# rwr_schematic.net
KiCad netlist of a schematic drawn in EAGLE
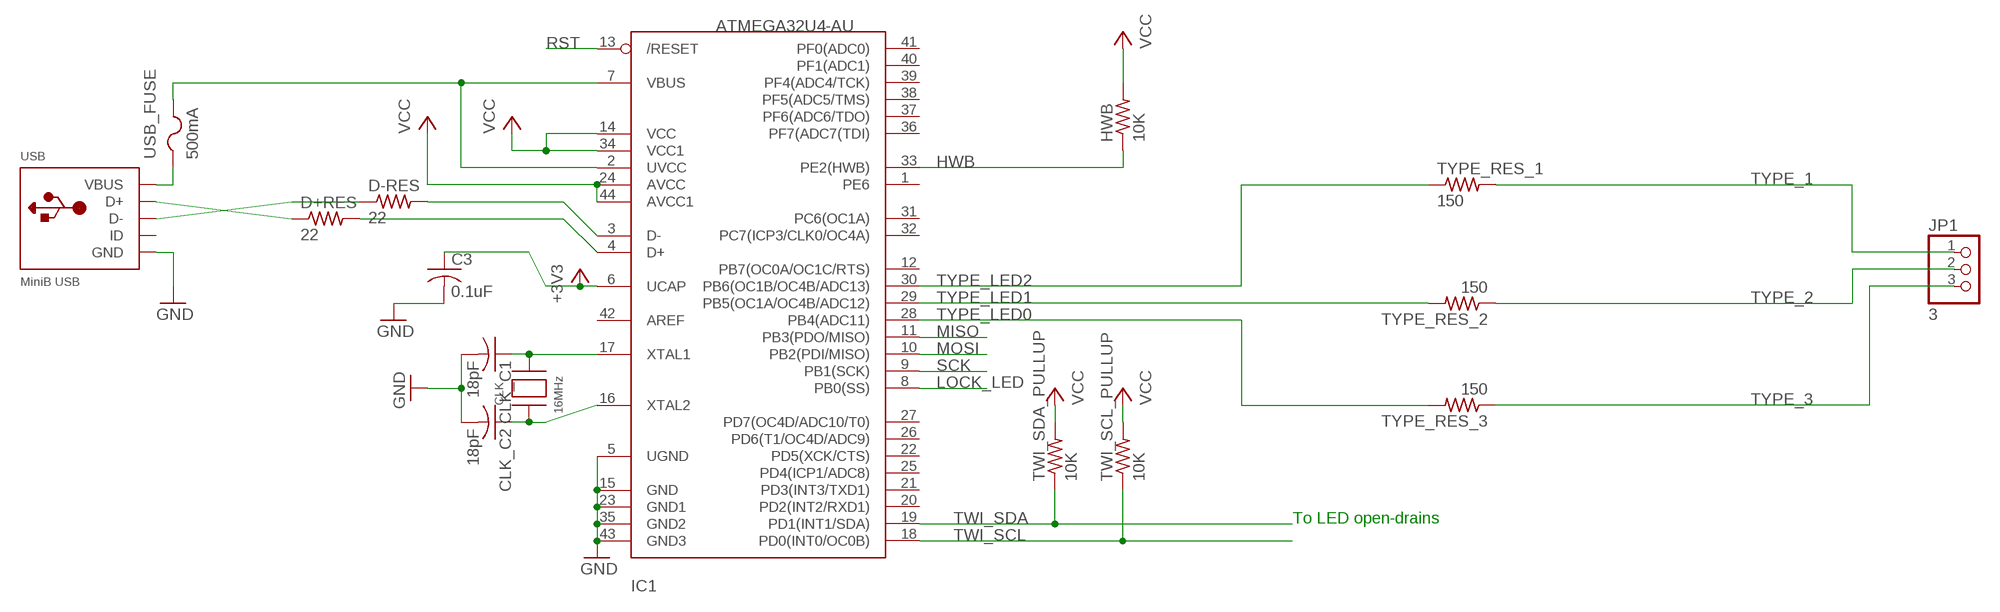
[diagram p0: schematic, sheet 1]
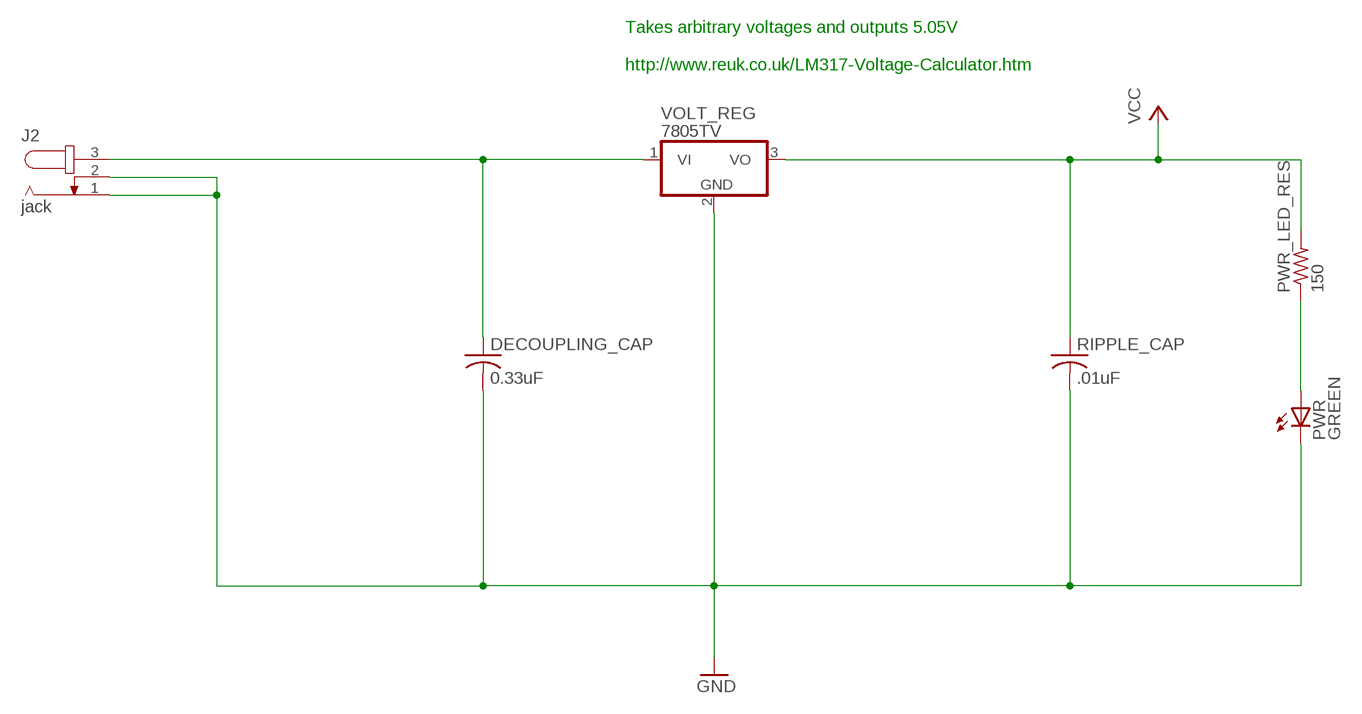
[diagram p1: schematic, sheet 2]
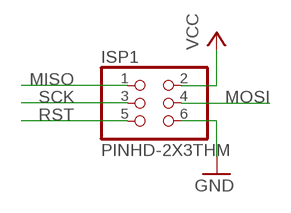
[diagram p2: schematic, sheet 3]
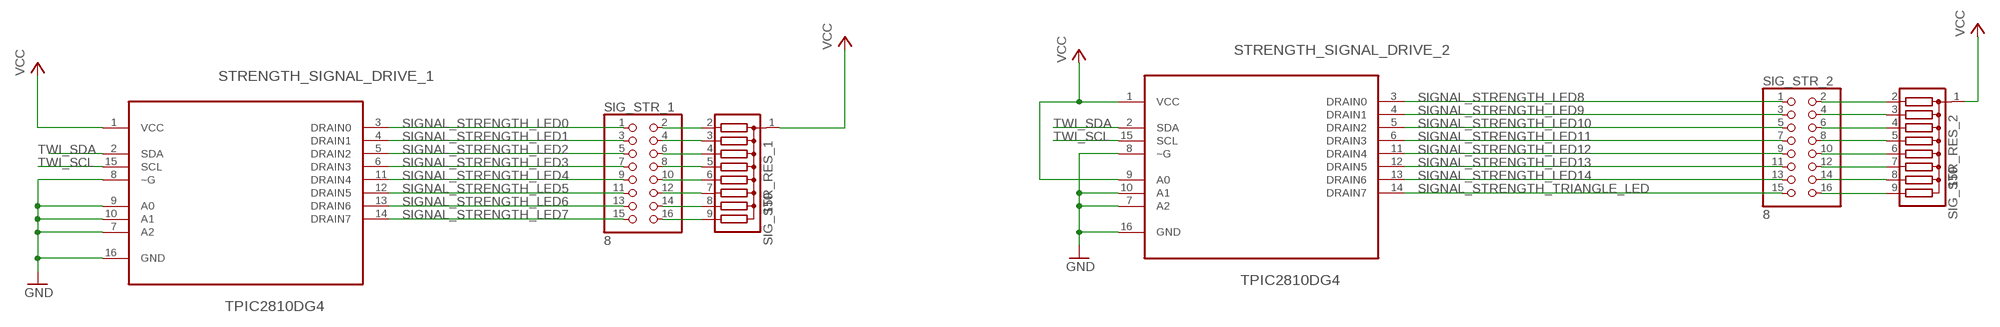
[diagram p3: schematic, sheet 4]
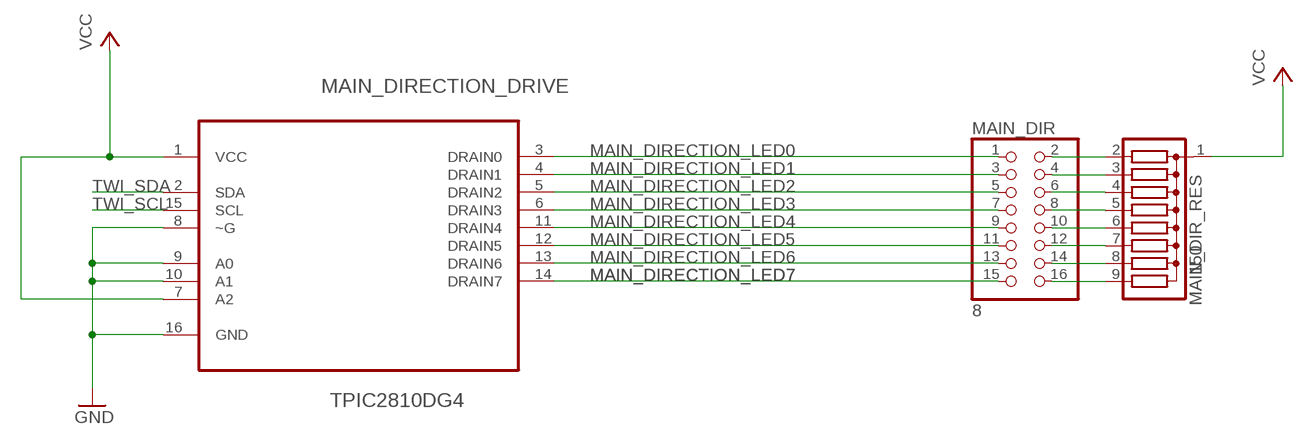
[diagram p4: schematic, sheet 5]
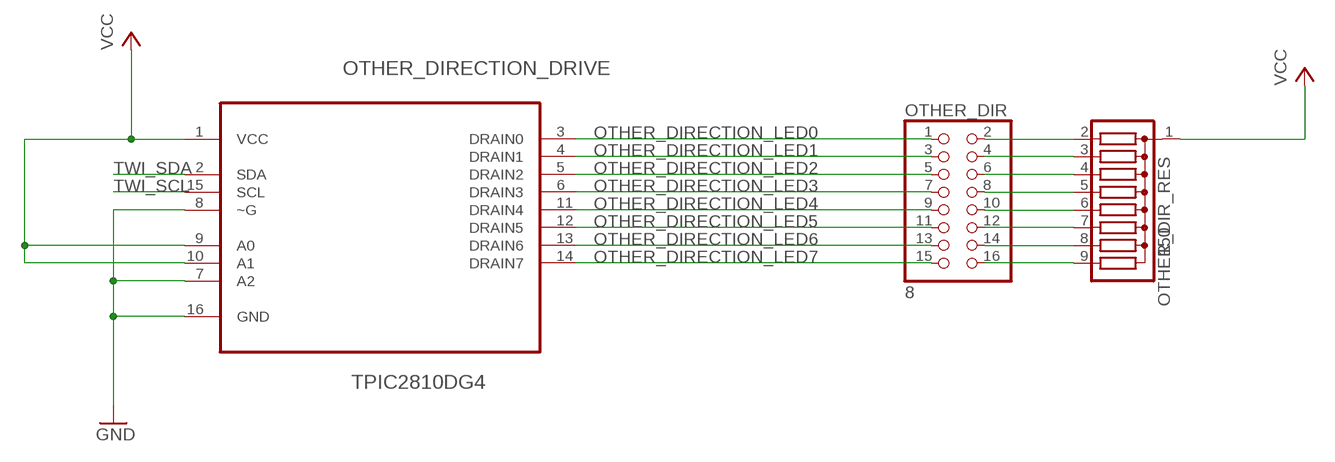
[diagram p5: schematic, sheet 6]
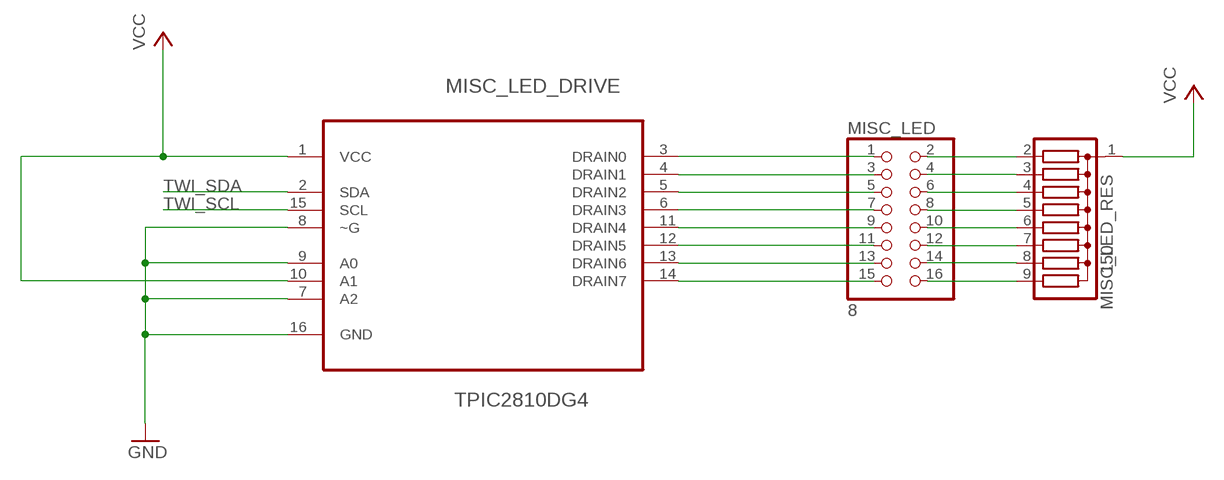
[diagram p6: schematic, sheet 7]
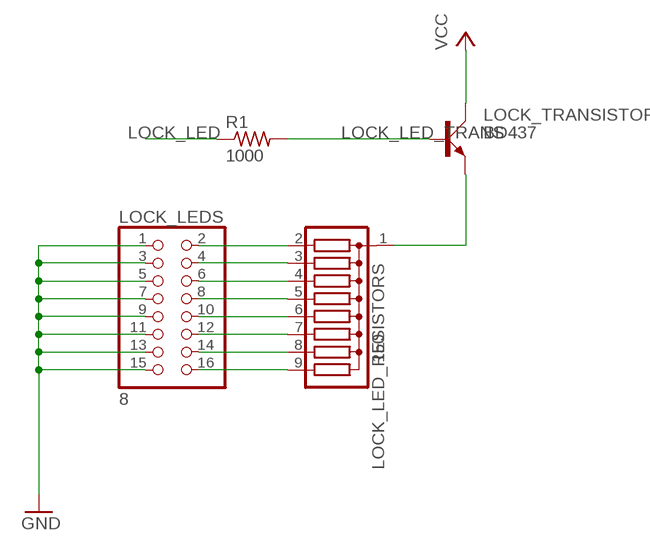
[diagram p7: schematic, sheet 8]

(export (version "E")
  (design (tool "Eeschema 10.0.6"))
  (components
    (comp (ref "MISC_LED")
      (value "8")
      (footprint "eagle-import:2X08")
      (libsource (lib "eagle-import") (part "PINHD-2X8"))
    )
    (comp (ref "MISC_LED_DRIVE")
      (value "TPIC2810DG4")
      (footprint "eagle-import:SOIC127P600X175-16N")
      (libsource (lib "eagle-import") (part "TPIC2810DG4"))
    )
    (comp (ref "MISC_LED_RES")
      (value "150")
      (footprint "eagle-import:SIL9")
      (libsource (lib "eagle-import") (part "G08R"))
    )
    (comp (ref "MAIN_DIR")
      (value "8")
      (footprint "eagle-import:2X08")
      (libsource (lib "eagle-import") (part "PINHD-2X8"))
    )
    (comp (ref "MAIN_DIRECTION_DRIVE")
      (value "TPIC2810DG4")
      (footprint "eagle-import:SOIC127P600X175-16N")
      (libsource (lib "eagle-import") (part "TPIC2810DG4"))
    )
    (comp (ref "MAIN_DIR_RES")
      (value "150")
      (footprint "eagle-import:SIL9")
      (libsource (lib "eagle-import") (part "G08R"))
    )
    (comp (ref "LOCK_LEDS")
      (value "8")
      (footprint "eagle-import:2X08")
      (libsource (lib "eagle-import") (part "PINHD-2X8"))
    )
    (comp (ref "LOCK_LED_RESISTORS")
      (value "150")
      (footprint "eagle-import:SIL9")
      (libsource (lib "eagle-import") (part "G08R"))
    )
    (comp (ref "LOCK_TRANSISTOR")
      (value "BD437")
      (footprint "eagle-import:TO126AV")
      (libsource (lib "eagle-import") (part "BD437"))
    )
    (comp (ref "R1")
      (value "1000")
      (footprint "eagle-import:R0805")
      (libsource (lib "eagle-import") (part "rcl_R-US_R0805"))
    )
    (comp (ref "C3")
      (value "0.1uF")
      (footprint "eagle-import:C0805K")
      (libsource (lib "eagle-import") (part "C-USC0805K"))
    )
    (comp (ref "CLK")
      (value "16MHz")
      (footprint "eagle-import:NX5032")
      (libsource (lib "eagle-import") (part "XTALNX5032"))
    )
    (comp (ref "CLK_C1")
      (value "18pF")
      (footprint "eagle-import:C0805K")
      (libsource (lib "eagle-import") (part "C-USC0805K"))
    )
    (comp (ref "CLK_C2")
      (value "18pF")
      (footprint "eagle-import:C0805K")
      (libsource (lib "eagle-import") (part "C-USC0805K"))
    )
    (comp (ref "D+RES")
      (value "22")
      (footprint "eagle-import:R0805")
      (libsource (lib "eagle-import") (part "R-US_R0805"))
    )
    (comp (ref "D-RES")
      (value "22")
      (footprint "eagle-import:R0805")
      (libsource (lib "eagle-import") (part "R-US_R0805"))
    )
    (comp (ref "HWB")
      (value "10K")
      (footprint "eagle-import:R0805")
      (libsource (lib "eagle-import") (part "R-US_R0805"))
    )
    (comp (ref "IC1")
      (value "ATMEGA32U4-AU")
      (footprint "eagle-import:TQFP44")
      (libsource (lib "eagle-import") (part "ATMEGA32U4-AU"))
    )
    (comp (ref "JP1")
      (value "3")
      (footprint "eagle-import:1X03")
      (libsource (lib "eagle-import") (part "PINHD-1X3"))
    )
    (comp (ref "TWI_SCL_PULLUP")
      (value "10K")
      (footprint "eagle-import:R0805")
      (libsource (lib "eagle-import") (part "R-US_R0805"))
    )
    (comp (ref "TWI_SDA_PULLUP")
      (value "10K")
      (footprint "eagle-import:R0805")
      (libsource (lib "eagle-import") (part "R-US_R0805"))
    )
    (comp (ref "TYPE_RES_1")
      (value "150")
      (footprint "eagle-import:R0805")
      (libsource (lib "eagle-import") (part "resistor_R-US_R0805"))
    )
    (comp (ref "TYPE_RES_2")
      (value "150")
      (footprint "eagle-import:R0805")
      (libsource (lib "eagle-import") (part "resistor_R-US_R0805"))
    )
    (comp (ref "TYPE_RES_3")
      (value "150")
      (footprint "eagle-import:R0805")
      (libsource (lib "eagle-import") (part "resistor_R-US_R0805"))
    )
    (comp (ref "USB")
      (value "MiniB USB")
      (footprint "eagle-import:USB-MINIB")
      (libsource (lib "eagle-import") (part "USBMINIB"))
    )
    (comp (ref "USB_FUSE")
      (value "500mA")
      (footprint "eagle-import:R1206")
      (libsource (lib "eagle-import") (part "PTCFUSE-1206"))
    )
    (comp (ref "DECOUPLING_CAP")
      (value "0.33uF")
      (footprint "eagle-import:C0805K")
      (libsource (lib "eagle-import") (part "C-USC0805K"))
    )
    (comp (ref "J2")
      (value "jack")
      (footprint "eagle-import:SPC4077")
      (libsource (lib "eagle-import") (part "JACK-PLUG0"))
    )
    (comp (ref "PWR")
      (value "GREEN")
      (footprint "eagle-import:CHIPLED_0805")
      (libsource (lib "eagle-import") (part "LEDCHIPLED_0805"))
    )
    (comp (ref "PWR_LED_RES")
      (value "150")
      (footprint "eagle-import:R0805")
      (libsource (lib "eagle-import") (part "R-US_R0805"))
    )
    (comp (ref "RIPPLE_CAP")
      (value ".01uF")
      (footprint "eagle-import:C0805K")
      (libsource (lib "eagle-import") (part "C-USC0805K"))
    )
    (comp (ref "VOLT_REG")
      (value "7805TV")
      (footprint "eagle-import:TO220V")
      (libsource (lib "eagle-import") (part "78TV05"))
    )
    (comp (ref "OTHER_DIR")
      (value "8")
      (footprint "eagle-import:2X08")
      (libsource (lib "eagle-import") (part "PINHD-2X8"))
    )
    (comp (ref "OTHER_DIRECTION_DRIVE")
      (value "TPIC2810DG4")
      (footprint "eagle-import:SOIC127P600X175-16N")
      (libsource (lib "eagle-import") (part "TPIC2810DG4"))
    )
    (comp (ref "OTHER_DIR_RES")
      (value "150")
      (footprint "eagle-import:SIL9")
      (libsource (lib "eagle-import") (part "G08R"))
    )
    (comp (ref "SIG_STR_1")
      (value "8")
      (footprint "eagle-import:2X08")
      (libsource (lib "eagle-import") (part "PINHD-2X8"))
    )
    (comp (ref "SIG_STR_2")
      (value "8")
      (footprint "eagle-import:2X08")
      (libsource (lib "eagle-import") (part "PINHD-2X8"))
    )
    (comp (ref "SIG_STR_RES_1")
      (value "150")
      (footprint "eagle-import:SIL9")
      (libsource (lib "eagle-import") (part "G08R"))
    )
    (comp (ref "SIG_STR_RES_2")
      (value "150")
      (footprint "eagle-import:SIL9")
      (libsource (lib "eagle-import") (part "G08R"))
    )
    (comp (ref "STRENGTH_SIGNAL_DRIVE_1")
      (value "TPIC2810DG4")
      (footprint "eagle-import:SOIC127P600X175-16N")
      (libsource (lib "eagle-import") (part "TPIC2810DG4"))
    )
    (comp (ref "STRENGTH_SIGNAL_DRIVE_2")
      (value "TPIC2810DG4")
      (footprint "eagle-import:SOIC127P600X175-16N")
      (libsource (lib "eagle-import") (part "TPIC2810DG4"))
    )
    (comp (ref "ISP1")
      (value "PINHD-2X3THM")
      (footprint "eagle-import:ISP6")
      (libsource (lib "eagle-import") (part "PINHD-2X3THM"))
    )
  )
  (nets
    (net (code "1") (name "+3V3") (class "Default")
      (node (ref "C3") (pin "1") (pinfunction "1_1") (pintype "passive"))
      (node (ref "IC1") (pin "6") (pinfunction "UCAP_6") (pintype "bidirectional"))
    )
    (net (code "2") (name "GND") (class "Default")
      (node (ref "C3") (pin "2") (pinfunction "2_2") (pintype "passive"))
      (node (ref "CLK_C1") (pin "2") (pinfunction "2_2") (pintype "passive"))
      (node (ref "CLK_C2") (pin "2") (pinfunction "2_2") (pintype "passive"))
      (node (ref "DECOUPLING_CAP") (pin "2") (pinfunction "2_2") (pintype "passive"))
      (node (ref "IC1") (pin "15") (pinfunction "GND_15") (pintype "bidirectional"))
      (node (ref "IC1") (pin "23") (pinfunction "GND1_23") (pintype "bidirectional"))
      (node (ref "IC1") (pin "35") (pinfunction "GND2_35") (pintype "bidirectional"))
      (node (ref "IC1") (pin "43") (pinfunction "GND3_43") (pintype "bidirectional"))
      (node (ref "IC1") (pin "5") (pinfunction "UGND_5") (pintype "bidirectional"))
      (node (ref "ISP1") (pin "6") (pinfunction "6_6") (pintype "passive"))
      (node (ref "J2") (pin "1") (pinfunction "1_1") (pintype "passive"))
      (node (ref "J2") (pin "2") (pinfunction "2_2") (pintype "passive"))
      (node (ref "LOCK_LEDS") (pin "1") (pinfunction "1_1") (pintype "passive"))
      (node (ref "LOCK_LEDS") (pin "11") (pinfunction "11_11") (pintype "passive"))
      (node (ref "LOCK_LEDS") (pin "13") (pinfunction "13_13") (pintype "passive"))
      (node (ref "LOCK_LEDS") (pin "15") (pinfunction "15_15") (pintype "passive"))
      (node (ref "LOCK_LEDS") (pin "3") (pinfunction "3_3") (pintype "passive"))
      (node (ref "LOCK_LEDS") (pin "5") (pinfunction "5_5") (pintype "passive"))
      (node (ref "LOCK_LEDS") (pin "7") (pinfunction "7_7") (pintype "passive"))
      (node (ref "LOCK_LEDS") (pin "9") (pinfunction "9_9") (pintype "passive"))
      (node (ref "MAIN_DIRECTION_DRIVE") (pin "10") (pinfunction "A1_10") (pintype "input"))
      (node (ref "MAIN_DIRECTION_DRIVE") (pin "16") (pinfunction "GND_16") (pintype "passive"))
      (node (ref "MAIN_DIRECTION_DRIVE") (pin "8") (pinfunction "~{G}_8") (pintype "input"))
      (node (ref "MAIN_DIRECTION_DRIVE") (pin "9") (pinfunction "A0_9") (pintype "input"))
      (node (ref "MISC_LED_DRIVE") (pin "16") (pinfunction "GND_16") (pintype "passive"))
      (node (ref "MISC_LED_DRIVE") (pin "7") (pinfunction "A2_7") (pintype "input"))
      (node (ref "MISC_LED_DRIVE") (pin "8") (pinfunction "~{G}_8") (pintype "input"))
      (node (ref "MISC_LED_DRIVE") (pin "9") (pinfunction "A0_9") (pintype "input"))
      (node (ref "OTHER_DIRECTION_DRIVE") (pin "16") (pinfunction "GND_16") (pintype "passive"))
      (node (ref "OTHER_DIRECTION_DRIVE") (pin "7") (pinfunction "A2_7") (pintype "input"))
      (node (ref "OTHER_DIRECTION_DRIVE") (pin "8") (pinfunction "~{G}_8") (pintype "input"))
      (node (ref "PWR") (pin "C") (pinfunction "C_C") (pintype "passive"))
      (node (ref "RIPPLE_CAP") (pin "2") (pinfunction "2_2") (pintype "passive"))
      (node (ref "STRENGTH_SIGNAL_DRIVE_1") (pin "10") (pinfunction "A1_10") (pintype "input"))
      (node (ref "STRENGTH_SIGNAL_DRIVE_1") (pin "16") (pinfunction "GND_16") (pintype "passive"))
      (node (ref "STRENGTH_SIGNAL_DRIVE_1") (pin "7") (pinfunction "A2_7") (pintype "input"))
      (node (ref "STRENGTH_SIGNAL_DRIVE_1") (pin "8") (pinfunction "~{G}_8") (pintype "input"))
      (node (ref "STRENGTH_SIGNAL_DRIVE_1") (pin "9") (pinfunction "A0_9") (pintype "input"))
      (node (ref "STRENGTH_SIGNAL_DRIVE_2") (pin "10") (pinfunction "A1_10") (pintype "input"))
      (node (ref "STRENGTH_SIGNAL_DRIVE_2") (pin "16") (pinfunction "GND_16") (pintype "passive"))
      (node (ref "STRENGTH_SIGNAL_DRIVE_2") (pin "7") (pinfunction "A2_7") (pintype "input"))
      (node (ref "STRENGTH_SIGNAL_DRIVE_2") (pin "8") (pinfunction "~{G}_8") (pintype "input"))
      (node (ref "USB") (pin "GND") (pinfunction "GND_GND") (pintype "power_in"))
      (node (ref "VOLT_REG") (pin "2") (pinfunction "GND_2") (pintype "passive"))
    )
    (net (code "3") (name "HWB") (class "Default")
      (node (ref "HWB") (pin "1") (pinfunction "1_1") (pintype "passive"))
      (node (ref "IC1") (pin "33") (pinfunction "PE2(HWB)_33") (pintype "bidirectional"))
    )
    (net (code "4") (name "LOCK_LED") (class "Default")
      (node (ref "IC1") (pin "8") (pinfunction "PB0(SS)_8") (pintype "bidirectional"))
      (node (ref "R1") (pin "1") (pinfunction "1_1") (pintype "passive"))
    )
    (net (code "5") (name "LOCK_LED_TRANS") (class "Default")
      (node (ref "LOCK_TRANSISTOR") (pin "B") (pinfunction "B_B") (pintype "passive"))
      (node (ref "R1") (pin "2") (pinfunction "2_2") (pintype "passive"))
    )
    (net (code "6") (name "MAIN_DIRECTION_LED0") (class "Default")
      (node (ref "MAIN_DIR") (pin "1") (pinfunction "1_1") (pintype "passive"))
      (node (ref "MAIN_DIRECTION_DRIVE") (pin "3") (pinfunction "DRAIN0_3") (pintype "output"))
    )
    (net (code "7") (name "MAIN_DIRECTION_LED1") (class "Default")
      (node (ref "MAIN_DIR") (pin "3") (pinfunction "3_3") (pintype "passive"))
      (node (ref "MAIN_DIRECTION_DRIVE") (pin "4") (pinfunction "DRAIN1_4") (pintype "output"))
    )
    (net (code "8") (name "MAIN_DIRECTION_LED2") (class "Default")
      (node (ref "MAIN_DIR") (pin "5") (pinfunction "5_5") (pintype "passive"))
      (node (ref "MAIN_DIRECTION_DRIVE") (pin "5") (pinfunction "DRAIN2_5") (pintype "output"))
    )
    (net (code "9") (name "MAIN_DIRECTION_LED3") (class "Default")
      (node (ref "MAIN_DIR") (pin "7") (pinfunction "7_7") (pintype "passive"))
      (node (ref "MAIN_DIRECTION_DRIVE") (pin "6") (pinfunction "DRAIN3_6") (pintype "output"))
    )
    (net (code "10") (name "MAIN_DIRECTION_LED4") (class "Default")
      (node (ref "MAIN_DIR") (pin "9") (pinfunction "9_9") (pintype "passive"))
      (node (ref "MAIN_DIRECTION_DRIVE") (pin "11") (pinfunction "DRAIN4_11") (pintype "output"))
    )
    (net (code "11") (name "MAIN_DIRECTION_LED5") (class "Default")
      (node (ref "MAIN_DIR") (pin "11") (pinfunction "11_11") (pintype "passive"))
      (node (ref "MAIN_DIRECTION_DRIVE") (pin "12") (pinfunction "DRAIN5_12") (pintype "output"))
    )
    (net (code "12") (name "MAIN_DIRECTION_LED6") (class "Default")
      (node (ref "MAIN_DIR") (pin "13") (pinfunction "13_13") (pintype "passive"))
      (node (ref "MAIN_DIRECTION_DRIVE") (pin "13") (pinfunction "DRAIN6_13") (pintype "output"))
    )
    (net (code "13") (name "MAIN_DIRECTION_LED7") (class "Default")
      (node (ref "MAIN_DIR") (pin "15") (pinfunction "15_15") (pintype "passive"))
      (node (ref "MAIN_DIRECTION_DRIVE") (pin "14") (pinfunction "DRAIN7_14") (pintype "output"))
    )
    (net (code "14") (name "MISO") (class "Default")
      (node (ref "IC1") (pin "11") (pinfunction "PB3(PDO/MISO)_11") (pintype "bidirectional"))
      (node (ref "ISP1") (pin "1") (pinfunction "1_1") (pintype "passive"))
    )
    (net (code "15") (name "MOSI") (class "Default")
      (node (ref "IC1") (pin "10") (pinfunction "PB2(PDI/MISO)_10") (pintype "bidirectional"))
      (node (ref "ISP1") (pin "4") (pinfunction "4_4") (pintype "passive"))
    )
    (net (code "16") (name "Net-(D+RES-Pad1)") (class "Default")
      (node (ref "D+RES") (pin "1") (pinfunction "1_1") (pintype "passive"))
      (node (ref "USB") (pin "D+") (pinfunction "D+_D+") (pintype "bidirectional"))
    )
    (net (code "17") (name "Net-(D-RES-Pad1)") (class "Default")
      (node (ref "D-RES") (pin "1") (pinfunction "1_1") (pintype "passive"))
      (node (ref "USB") (pin "D-") (pinfunction "D-_D-") (pintype "bidirectional"))
    )
    (net (code "18") (name "Net-(IC1-D+)") (class "Default")
      (node (ref "D+RES") (pin "2") (pinfunction "2_2") (pintype "passive"))
      (node (ref "IC1") (pin "4") (pinfunction "D+_4") (pintype "bidirectional"))
    )
    (net (code "19") (name "Net-(IC1-D-)") (class "Default")
      (node (ref "D-RES") (pin "2") (pinfunction "2_2") (pintype "passive"))
      (node (ref "IC1") (pin "3") (pinfunction "D-_3") (pintype "bidirectional"))
    )
    (net (code "20") (name "Net-(IC1-UVCC)") (class "Default")
      (node (ref "IC1") (pin "2") (pinfunction "UVCC_2") (pintype "bidirectional"))
      (node (ref "IC1") (pin "7") (pinfunction "VBUS_7") (pintype "bidirectional"))
      (node (ref "USB_FUSE") (pin "2") (pinfunction "2_2") (pintype "passive"))
    )
    (net (code "21") (name "Net-(IC1-XTAL1)") (class "Default")
      (node (ref "CLK") (pin "P$2") (pinfunction "P$2_P$2") (pintype "bidirectional"))
      (node (ref "CLK_C1") (pin "1") (pinfunction "1_1") (pintype "passive"))
      (node (ref "IC1") (pin "17") (pinfunction "XTAL1_17") (pintype "bidirectional"))
    )
    (net (code "22") (name "Net-(IC1-XTAL2)") (class "Default")
      (node (ref "CLK") (pin "P$1") (pinfunction "P$1_P$1") (pintype "bidirectional"))
      (node (ref "CLK_C2") (pin "1") (pinfunction "1_1") (pintype "passive"))
      (node (ref "IC1") (pin "16") (pinfunction "XTAL2_16") (pintype "bidirectional"))
    )
    (net (code "23") (name "Net-(LOCK_LEDS-Pad2)") (class "Default")
      (node (ref "LOCK_LEDS") (pin "2") (pinfunction "2_2") (pintype "passive"))
      (node (ref "LOCK_LED_RESISTORS") (pin "2") (pinfunction "2_2") (pintype "passive"))
    )
    (net (code "24") (name "Net-(LOCK_LEDS-Pad4)") (class "Default")
      (node (ref "LOCK_LEDS") (pin "4") (pinfunction "4_4") (pintype "passive"))
      (node (ref "LOCK_LED_RESISTORS") (pin "3") (pinfunction "3_3") (pintype "passive"))
    )
    (net (code "25") (name "Net-(LOCK_LEDS-Pad6)") (class "Default")
      (node (ref "LOCK_LEDS") (pin "6") (pinfunction "6_6") (pintype "passive"))
      (node (ref "LOCK_LED_RESISTORS") (pin "4") (pinfunction "4_4") (pintype "passive"))
    )
    (net (code "26") (name "Net-(LOCK_LEDS-Pad8)") (class "Default")
      (node (ref "LOCK_LEDS") (pin "8") (pinfunction "8_8") (pintype "passive"))
      (node (ref "LOCK_LED_RESISTORS") (pin "5") (pinfunction "5_5") (pintype "passive"))
    )
    (net (code "27") (name "Net-(LOCK_LEDS-Pad10)") (class "Default")
      (node (ref "LOCK_LEDS") (pin "10") (pinfunction "10_10") (pintype "passive"))
      (node (ref "LOCK_LED_RESISTORS") (pin "6") (pinfunction "6_6") (pintype "passive"))
    )
    (net (code "28") (name "Net-(LOCK_LEDS-Pad12)") (class "Default")
      (node (ref "LOCK_LEDS") (pin "12") (pinfunction "12_12") (pintype "passive"))
      (node (ref "LOCK_LED_RESISTORS") (pin "7") (pinfunction "7_7") (pintype "passive"))
    )
    (net (code "29") (name "Net-(LOCK_LEDS-Pad14)") (class "Default")
      (node (ref "LOCK_LEDS") (pin "14") (pinfunction "14_14") (pintype "passive"))
      (node (ref "LOCK_LED_RESISTORS") (pin "8") (pinfunction "8_8") (pintype "passive"))
    )
    (net (code "30") (name "Net-(LOCK_LEDS-Pad16)") (class "Default")
      (node (ref "LOCK_LEDS") (pin "16") (pinfunction "16_16") (pintype "passive"))
      (node (ref "LOCK_LED_RESISTORS") (pin "9") (pinfunction "9_9") (pintype "passive"))
    )
    (net (code "31") (name "Net-(LOCK_LED_RESISTORS-Pad1)") (class "Default")
      (node (ref "LOCK_LED_RESISTORS") (pin "1") (pinfunction "1_1") (pintype "passive"))
      (node (ref "LOCK_TRANSISTOR") (pin "E") (pinfunction "E_E") (pintype "passive"))
    )
    (net (code "32") (name "Net-(MAIN_DIR-Pad2)") (class "Default")
      (node (ref "MAIN_DIR") (pin "2") (pinfunction "2_2") (pintype "passive"))
      (node (ref "MAIN_DIR_RES") (pin "2") (pinfunction "2_2") (pintype "passive"))
    )
    (net (code "33") (name "Net-(MAIN_DIR-Pad4)") (class "Default")
      (node (ref "MAIN_DIR") (pin "4") (pinfunction "4_4") (pintype "passive"))
      (node (ref "MAIN_DIR_RES") (pin "3") (pinfunction "3_3") (pintype "passive"))
    )
    (net (code "34") (name "Net-(MAIN_DIR-Pad6)") (class "Default")
      (node (ref "MAIN_DIR") (pin "6") (pinfunction "6_6") (pintype "passive"))
      (node (ref "MAIN_DIR_RES") (pin "4") (pinfunction "4_4") (pintype "passive"))
    )
    (net (code "35") (name "Net-(MAIN_DIR-Pad8)") (class "Default")
      (node (ref "MAIN_DIR") (pin "8") (pinfunction "8_8") (pintype "passive"))
      (node (ref "MAIN_DIR_RES") (pin "5") (pinfunction "5_5") (pintype "passive"))
    )
    (net (code "36") (name "Net-(MAIN_DIR-Pad10)") (class "Default")
      (node (ref "MAIN_DIR") (pin "10") (pinfunction "10_10") (pintype "passive"))
      (node (ref "MAIN_DIR_RES") (pin "6") (pinfunction "6_6") (pintype "passive"))
    )
    (net (code "37") (name "Net-(MAIN_DIR-Pad12)") (class "Default")
      (node (ref "MAIN_DIR") (pin "12") (pinfunction "12_12") (pintype "passive"))
      (node (ref "MAIN_DIR_RES") (pin "7") (pinfunction "7_7") (pintype "passive"))
    )
    (net (code "38") (name "Net-(MAIN_DIR-Pad14)") (class "Default")
      (node (ref "MAIN_DIR") (pin "14") (pinfunction "14_14") (pintype "passive"))
      (node (ref "MAIN_DIR_RES") (pin "8") (pinfunction "8_8") (pintype "passive"))
    )
    (net (code "39") (name "Net-(MAIN_DIR-Pad16)") (class "Default")
      (node (ref "MAIN_DIR") (pin "16") (pinfunction "16_16") (pintype "passive"))
      (node (ref "MAIN_DIR_RES") (pin "9") (pinfunction "9_9") (pintype "passive"))
    )
    (net (code "40") (name "Net-(MISC_LED-Pad2)") (class "Default")
      (node (ref "MISC_LED") (pin "2") (pinfunction "2_2") (pintype "passive"))
      (node (ref "MISC_LED_RES") (pin "2") (pinfunction "2_2") (pintype "passive"))
    )
    (net (code "41") (name "Net-(MISC_LED-Pad4)") (class "Default")
      (node (ref "MISC_LED") (pin "4") (pinfunction "4_4") (pintype "passive"))
      (node (ref "MISC_LED_RES") (pin "3") (pinfunction "3_3") (pintype "passive"))
    )
    (net (code "42") (name "Net-(MISC_LED-Pad6)") (class "Default")
      (node (ref "MISC_LED") (pin "6") (pinfunction "6_6") (pintype "passive"))
      (node (ref "MISC_LED_RES") (pin "4") (pinfunction "4_4") (pintype "passive"))
    )
    (net (code "43") (name "Net-(MISC_LED-Pad8)") (class "Default")
      (node (ref "MISC_LED") (pin "8") (pinfunction "8_8") (pintype "passive"))
      (node (ref "MISC_LED_RES") (pin "5") (pinfunction "5_5") (pintype "passive"))
    )
    (net (code "44") (name "Net-(MISC_LED-Pad10)") (class "Default")
      (node (ref "MISC_LED") (pin "10") (pinfunction "10_10") (pintype "passive"))
      (node (ref "MISC_LED_RES") (pin "6") (pinfunction "6_6") (pintype "passive"))
    )
    (net (code "45") (name "Net-(MISC_LED-Pad12)") (class "Default")
      (node (ref "MISC_LED") (pin "12") (pinfunction "12_12") (pintype "passive"))
      (node (ref "MISC_LED_RES") (pin "7") (pinfunction "7_7") (pintype "passive"))
    )
    (net (code "46") (name "Net-(MISC_LED-Pad14)") (class "Default")
      (node (ref "MISC_LED") (pin "14") (pinfunction "14_14") (pintype "passive"))
      (node (ref "MISC_LED_RES") (pin "8") (pinfunction "8_8") (pintype "passive"))
    )
    (net (code "47") (name "Net-(MISC_LED-Pad16)") (class "Default")
      (node (ref "MISC_LED") (pin "16") (pinfunction "16_16") (pintype "passive"))
      (node (ref "MISC_LED_RES") (pin "9") (pinfunction "9_9") (pintype "passive"))
    )
    (net (code "48") (name "Net-(MISC_LED_DRIVE-DRAIN0)") (class "Default")
      (node (ref "MISC_LED") (pin "1") (pinfunction "1_1") (pintype "passive"))
      (node (ref "MISC_LED_DRIVE") (pin "3") (pinfunction "DRAIN0_3") (pintype "output"))
    )
    (net (code "49") (name "Net-(MISC_LED_DRIVE-DRAIN1)") (class "Default")
      (node (ref "MISC_LED") (pin "3") (pinfunction "3_3") (pintype "passive"))
      (node (ref "MISC_LED_DRIVE") (pin "4") (pinfunction "DRAIN1_4") (pintype "output"))
    )
    (net (code "50") (name "Net-(MISC_LED_DRIVE-DRAIN2)") (class "Default")
      (node (ref "MISC_LED") (pin "5") (pinfunction "5_5") (pintype "passive"))
      (node (ref "MISC_LED_DRIVE") (pin "5") (pinfunction "DRAIN2_5") (pintype "output"))
    )
    (net (code "51") (name "Net-(MISC_LED_DRIVE-DRAIN3)") (class "Default")
      (node (ref "MISC_LED") (pin "7") (pinfunction "7_7") (pintype "passive"))
      (node (ref "MISC_LED_DRIVE") (pin "6") (pinfunction "DRAIN3_6") (pintype "output"))
    )
    (net (code "52") (name "Net-(MISC_LED_DRIVE-DRAIN4)") (class "Default")
      (node (ref "MISC_LED") (pin "9") (pinfunction "9_9") (pintype "passive"))
      (node (ref "MISC_LED_DRIVE") (pin "11") (pinfunction "DRAIN4_11") (pintype "output"))
    )
    (net (code "53") (name "Net-(MISC_LED_DRIVE-DRAIN5)") (class "Default")
      (node (ref "MISC_LED") (pin "11") (pinfunction "11_11") (pintype "passive"))
      (node (ref "MISC_LED_DRIVE") (pin "12") (pinfunction "DRAIN5_12") (pintype "output"))
    )
    (net (code "54") (name "Net-(MISC_LED_DRIVE-DRAIN6)") (class "Default")
      (node (ref "MISC_LED") (pin "13") (pinfunction "13_13") (pintype "passive"))
      (node (ref "MISC_LED_DRIVE") (pin "13") (pinfunction "DRAIN6_13") (pintype "output"))
    )
    (net (code "55") (name "Net-(MISC_LED_DRIVE-DRAIN7)") (class "Default")
      (node (ref "MISC_LED") (pin "15") (pinfunction "15_15") (pintype "passive"))
      (node (ref "MISC_LED_DRIVE") (pin "14") (pinfunction "DRAIN7_14") (pintype "output"))
    )
    (net (code "56") (name "Net-(OTHER_DIR-Pad2)") (class "Default")
      (node (ref "OTHER_DIR") (pin "2") (pinfunction "2_2") (pintype "passive"))
      (node (ref "OTHER_DIR_RES") (pin "2") (pinfunction "2_2") (pintype "passive"))
    )
    (net (code "57") (name "Net-(OTHER_DIR-Pad4)") (class "Default")
      (node (ref "OTHER_DIR") (pin "4") (pinfunction "4_4") (pintype "passive"))
      (node (ref "OTHER_DIR_RES") (pin "3") (pinfunction "3_3") (pintype "passive"))
    )
    (net (code "58") (name "Net-(OTHER_DIR-Pad6)") (class "Default")
      (node (ref "OTHER_DIR") (pin "6") (pinfunction "6_6") (pintype "passive"))
      (node (ref "OTHER_DIR_RES") (pin "4") (pinfunction "4_4") (pintype "passive"))
    )
    (net (code "59") (name "Net-(OTHER_DIR-Pad8)") (class "Default")
      (node (ref "OTHER_DIR") (pin "8") (pinfunction "8_8") (pintype "passive"))
      (node (ref "OTHER_DIR_RES") (pin "5") (pinfunction "5_5") (pintype "passive"))
    )
    (net (code "60") (name "Net-(OTHER_DIR-Pad10)") (class "Default")
      (node (ref "OTHER_DIR") (pin "10") (pinfunction "10_10") (pintype "passive"))
      (node (ref "OTHER_DIR_RES") (pin "6") (pinfunction "6_6") (pintype "passive"))
    )
    (net (code "61") (name "Net-(OTHER_DIR-Pad12)") (class "Default")
      (node (ref "OTHER_DIR") (pin "12") (pinfunction "12_12") (pintype "passive"))
      (node (ref "OTHER_DIR_RES") (pin "7") (pinfunction "7_7") (pintype "passive"))
    )
    (net (code "62") (name "Net-(OTHER_DIR-Pad14)") (class "Default")
      (node (ref "OTHER_DIR") (pin "14") (pinfunction "14_14") (pintype "passive"))
      (node (ref "OTHER_DIR_RES") (pin "8") (pinfunction "8_8") (pintype "passive"))
    )
    (net (code "63") (name "Net-(OTHER_DIR-Pad16)") (class "Default")
      (node (ref "OTHER_DIR") (pin "16") (pinfunction "16_16") (pintype "passive"))
      (node (ref "OTHER_DIR_RES") (pin "9") (pinfunction "9_9") (pintype "passive"))
    )
    (net (code "64") (name "Net-(PWR-PadA)") (class "Default")
      (node (ref "PWR") (pin "A") (pinfunction "A_A") (pintype "passive"))
      (node (ref "PWR_LED_RES") (pin "1") (pinfunction "1_1") (pintype "passive"))
    )
    (net (code "65") (name "Net-(SIG_STR_1-Pad2)") (class "Default")
      (node (ref "SIG_STR_1") (pin "2") (pinfunction "2_2") (pintype "passive"))
      (node (ref "SIG_STR_RES_1") (pin "2") (pinfunction "2_2") (pintype "passive"))
    )
    (net (code "66") (name "Net-(SIG_STR_1-Pad4)") (class "Default")
      (node (ref "SIG_STR_1") (pin "4") (pinfunction "4_4") (pintype "passive"))
      (node (ref "SIG_STR_RES_1") (pin "3") (pinfunction "3_3") (pintype "passive"))
    )
    (net (code "67") (name "Net-(SIG_STR_1-Pad6)") (class "Default")
      (node (ref "SIG_STR_1") (pin "6") (pinfunction "6_6") (pintype "passive"))
      (node (ref "SIG_STR_RES_1") (pin "4") (pinfunction "4_4") (pintype "passive"))
    )
    (net (code "68") (name "Net-(SIG_STR_1-Pad8)") (class "Default")
      (node (ref "SIG_STR_1") (pin "8") (pinfunction "8_8") (pintype "passive"))
      (node (ref "SIG_STR_RES_1") (pin "5") (pinfunction "5_5") (pintype "passive"))
    )
    (net (code "69") (name "Net-(SIG_STR_1-Pad10)") (class "Default")
      (node (ref "SIG_STR_1") (pin "10") (pinfunction "10_10") (pintype "passive"))
      (node (ref "SIG_STR_RES_1") (pin "6") (pinfunction "6_6") (pintype "passive"))
    )
    (net (code "70") (name "Net-(SIG_STR_1-Pad12)") (class "Default")
      (node (ref "SIG_STR_1") (pin "12") (pinfunction "12_12") (pintype "passive"))
      (node (ref "SIG_STR_RES_1") (pin "7") (pinfunction "7_7") (pintype "passive"))
    )
    (net (code "71") (name "Net-(SIG_STR_1-Pad14)") (class "Default")
      (node (ref "SIG_STR_1") (pin "14") (pinfunction "14_14") (pintype "passive"))
      (node (ref "SIG_STR_RES_1") (pin "8") (pinfunction "8_8") (pintype "passive"))
    )
    (net (code "72") (name "Net-(SIG_STR_1-Pad16)") (class "Default")
      (node (ref "SIG_STR_1") (pin "16") (pinfunction "16_16") (pintype "passive"))
      (node (ref "SIG_STR_RES_1") (pin "9") (pinfunction "9_9") (pintype "passive"))
    )
    (net (code "73") (name "Net-(SIG_STR_2-Pad2)") (class "Default")
      (node (ref "SIG_STR_2") (pin "2") (pinfunction "2_2") (pintype "passive"))
      (node (ref "SIG_STR_RES_2") (pin "2") (pinfunction "2_2") (pintype "passive"))
    )
    (net (code "74") (name "Net-(SIG_STR_2-Pad4)") (class "Default")
      (node (ref "SIG_STR_2") (pin "4") (pinfunction "4_4") (pintype "passive"))
      (node (ref "SIG_STR_RES_2") (pin "3") (pinfunction "3_3") (pintype "passive"))
    )
    (net (code "75") (name "Net-(SIG_STR_2-Pad6)") (class "Default")
      (node (ref "SIG_STR_2") (pin "6") (pinfunction "6_6") (pintype "passive"))
      (node (ref "SIG_STR_RES_2") (pin "4") (pinfunction "4_4") (pintype "passive"))
    )
    (net (code "76") (name "Net-(SIG_STR_2-Pad8)") (class "Default")
      (node (ref "SIG_STR_2") (pin "8") (pinfunction "8_8") (pintype "passive"))
      (node (ref "SIG_STR_RES_2") (pin "5") (pinfunction "5_5") (pintype "passive"))
    )
    (net (code "77") (name "Net-(SIG_STR_2-Pad10)") (class "Default")
      (node (ref "SIG_STR_2") (pin "10") (pinfunction "10_10") (pintype "passive"))
      (node (ref "SIG_STR_RES_2") (pin "6") (pinfunction "6_6") (pintype "passive"))
    )
    (net (code "78") (name "Net-(SIG_STR_2-Pad12)") (class "Default")
      (node (ref "SIG_STR_2") (pin "12") (pinfunction "12_12") (pintype "passive"))
      (node (ref "SIG_STR_RES_2") (pin "7") (pinfunction "7_7") (pintype "passive"))
    )
    (net (code "79") (name "Net-(SIG_STR_2-Pad14)") (class "Default")
      (node (ref "SIG_STR_2") (pin "14") (pinfunction "14_14") (pintype "passive"))
      (node (ref "SIG_STR_RES_2") (pin "8") (pinfunction "8_8") (pintype "passive"))
    )
    (net (code "80") (name "Net-(SIG_STR_2-Pad16)") (class "Default")
      (node (ref "SIG_STR_2") (pin "16") (pinfunction "16_16") (pintype "passive"))
      (node (ref "SIG_STR_RES_2") (pin "9") (pinfunction "9_9") (pintype "passive"))
    )
    (net (code "81") (name "Net-(USB-PadVBUS)") (class "Default")
      (node (ref "USB") (pin "VBUS") (pinfunction "VBUS_VBUS") (pintype "power_in"))
      (node (ref "USB_FUSE") (pin "1") (pinfunction "1_1") (pintype "passive"))
    )
    (net (code "82") (name "Net-(VOLT_REG-VI)") (class "Default")
      (node (ref "DECOUPLING_CAP") (pin "1") (pinfunction "1_1") (pintype "passive"))
      (node (ref "J2") (pin "3") (pinfunction "3_3") (pintype "passive"))
      (node (ref "VOLT_REG") (pin "1") (pinfunction "VI_1") (pintype "input"))
    )
    (net (code "83") (name "OTHER_DIRECTION_LED0") (class "Default")
      (node (ref "OTHER_DIR") (pin "1") (pinfunction "1_1") (pintype "passive"))
      (node (ref "OTHER_DIRECTION_DRIVE") (pin "3") (pinfunction "DRAIN0_3") (pintype "output"))
    )
    (net (code "84") (name "OTHER_DIRECTION_LED1") (class "Default")
      (node (ref "OTHER_DIR") (pin "3") (pinfunction "3_3") (pintype "passive"))
      (node (ref "OTHER_DIRECTION_DRIVE") (pin "4") (pinfunction "DRAIN1_4") (pintype "output"))
    )
    (net (code "85") (name "OTHER_DIRECTION_LED2") (class "Default")
      (node (ref "OTHER_DIR") (pin "5") (pinfunction "5_5") (pintype "passive"))
      (node (ref "OTHER_DIRECTION_DRIVE") (pin "5") (pinfunction "DRAIN2_5") (pintype "output"))
    )
    (net (code "86") (name "OTHER_DIRECTION_LED3") (class "Default")
      (node (ref "OTHER_DIR") (pin "7") (pinfunction "7_7") (pintype "passive"))
      (node (ref "OTHER_DIRECTION_DRIVE") (pin "6") (pinfunction "DRAIN3_6") (pintype "output"))
    )
    (net (code "87") (name "OTHER_DIRECTION_LED4") (class "Default")
      (node (ref "OTHER_DIR") (pin "9") (pinfunction "9_9") (pintype "passive"))
      (node (ref "OTHER_DIRECTION_DRIVE") (pin "11") (pinfunction "DRAIN4_11") (pintype "output"))
    )
    (net (code "88") (name "OTHER_DIRECTION_LED5") (class "Default")
      (node (ref "OTHER_DIR") (pin "11") (pinfunction "11_11") (pintype "passive"))
      (node (ref "OTHER_DIRECTION_DRIVE") (pin "12") (pinfunction "DRAIN5_12") (pintype "output"))
    )
    (net (code "89") (name "OTHER_DIRECTION_LED6") (class "Default")
      (node (ref "OTHER_DIR") (pin "13") (pinfunction "13_13") (pintype "passive"))
      (node (ref "OTHER_DIRECTION_DRIVE") (pin "13") (pinfunction "DRAIN6_13") (pintype "output"))
    )
    (net (code "90") (name "OTHER_DIRECTION_LED7") (class "Default")
      (node (ref "OTHER_DIR") (pin "15") (pinfunction "15_15") (pintype "passive"))
      (node (ref "OTHER_DIRECTION_DRIVE") (pin "14") (pinfunction "DRAIN7_14") (pintype "output"))
    )
    (net (code "91") (name "RST") (class "Default")
      (node (ref "IC1") (pin "13") (pinfunction "/RESET_13") (pintype "bidirectional"))
      (node (ref "ISP1") (pin "5") (pinfunction "5_5") (pintype "passive"))
    )
    (net (code "92") (name "SCK") (class "Default")
      (node (ref "IC1") (pin "9") (pinfunction "PB1(SCK)_9") (pintype "bidirectional"))
      (node (ref "ISP1") (pin "3") (pinfunction "3_3") (pintype "passive"))
    )
    (net (code "93") (name "SIGNAL_STRENGTH_LED0") (class "Default")
      (node (ref "SIG_STR_1") (pin "1") (pinfunction "1_1") (pintype "passive"))
      (node (ref "STRENGTH_SIGNAL_DRIVE_1") (pin "3") (pinfunction "DRAIN0_3") (pintype "output"))
    )
    (net (code "94") (name "SIGNAL_STRENGTH_LED1") (class "Default")
      (node (ref "SIG_STR_1") (pin "3") (pinfunction "3_3") (pintype "passive"))
      (node (ref "STRENGTH_SIGNAL_DRIVE_1") (pin "4") (pinfunction "DRAIN1_4") (pintype "output"))
    )
    (net (code "95") (name "SIGNAL_STRENGTH_LED2") (class "Default")
      (node (ref "SIG_STR_1") (pin "5") (pinfunction "5_5") (pintype "passive"))
      (node (ref "STRENGTH_SIGNAL_DRIVE_1") (pin "5") (pinfunction "DRAIN2_5") (pintype "output"))
    )
    (net (code "96") (name "SIGNAL_STRENGTH_LED3") (class "Default")
      (node (ref "SIG_STR_1") (pin "7") (pinfunction "7_7") (pintype "passive"))
      (node (ref "STRENGTH_SIGNAL_DRIVE_1") (pin "6") (pinfunction "DRAIN3_6") (pintype "output"))
    )
    (net (code "97") (name "SIGNAL_STRENGTH_LED4") (class "Default")
      (node (ref "SIG_STR_1") (pin "9") (pinfunction "9_9") (pintype "passive"))
      (node (ref "STRENGTH_SIGNAL_DRIVE_1") (pin "11") (pinfunction "DRAIN4_11") (pintype "output"))
    )
    (net (code "98") (name "SIGNAL_STRENGTH_LED5") (class "Default")
      (node (ref "SIG_STR_1") (pin "11") (pinfunction "11_11") (pintype "passive"))
      (node (ref "STRENGTH_SIGNAL_DRIVE_1") (pin "12") (pinfunction "DRAIN5_12") (pintype "output"))
    )
    (net (code "99") (name "SIGNAL_STRENGTH_LED6") (class "Default")
      (node (ref "SIG_STR_1") (pin "13") (pinfunction "13_13") (pintype "passive"))
      (node (ref "STRENGTH_SIGNAL_DRIVE_1") (pin "13") (pinfunction "DRAIN6_13") (pintype "output"))
    )
    (net (code "100") (name "SIGNAL_STRENGTH_LED7") (class "Default")
      (node (ref "SIG_STR_1") (pin "15") (pinfunction "15_15") (pintype "passive"))
      (node (ref "STRENGTH_SIGNAL_DRIVE_1") (pin "14") (pinfunction "DRAIN7_14") (pintype "output"))
    )
    (net (code "101") (name "SIGNAL_STRENGTH_LED8") (class "Default")
      (node (ref "SIG_STR_2") (pin "1") (pinfunction "1_1") (pintype "passive"))
      (node (ref "STRENGTH_SIGNAL_DRIVE_2") (pin "3") (pinfunction "DRAIN0_3") (pintype "output"))
    )
    (net (code "102") (name "SIGNAL_STRENGTH_LED9") (class "Default")
      (node (ref "SIG_STR_2") (pin "3") (pinfunction "3_3") (pintype "passive"))
      (node (ref "STRENGTH_SIGNAL_DRIVE_2") (pin "4") (pinfunction "DRAIN1_4") (pintype "output"))
    )
    (net (code "103") (name "SIGNAL_STRENGTH_LED10") (class "Default")
      (node (ref "SIG_STR_2") (pin "5") (pinfunction "5_5") (pintype "passive"))
      (node (ref "STRENGTH_SIGNAL_DRIVE_2") (pin "5") (pinfunction "DRAIN2_5") (pintype "output"))
    )
    (net (code "104") (name "SIGNAL_STRENGTH_LED11") (class "Default")
      (node (ref "SIG_STR_2") (pin "7") (pinfunction "7_7") (pintype "passive"))
      (node (ref "STRENGTH_SIGNAL_DRIVE_2") (pin "6") (pinfunction "DRAIN3_6") (pintype "output"))
    )
    (net (code "105") (name "SIGNAL_STRENGTH_LED12") (class "Default")
      (node (ref "SIG_STR_2") (pin "9") (pinfunction "9_9") (pintype "passive"))
      (node (ref "STRENGTH_SIGNAL_DRIVE_2") (pin "11") (pinfunction "DRAIN4_11") (pintype "output"))
    )
    (net (code "106") (name "SIGNAL_STRENGTH_LED13") (class "Default")
      (node (ref "SIG_STR_2") (pin "11") (pinfunction "11_11") (pintype "passive"))
      (node (ref "STRENGTH_SIGNAL_DRIVE_2") (pin "12") (pinfunction "DRAIN5_12") (pintype "output"))
    )
    (net (code "107") (name "SIGNAL_STRENGTH_LED14") (class "Default")
      (node (ref "SIG_STR_2") (pin "13") (pinfunction "13_13") (pintype "passive"))
      (node (ref "STRENGTH_SIGNAL_DRIVE_2") (pin "13") (pinfunction "DRAIN6_13") (pintype "output"))
    )
    (net (code "108") (name "SIGNAL_STRENGTH_TRIANGLE_LED") (class "Default")
      (node (ref "SIG_STR_2") (pin "15") (pinfunction "15_15") (pintype "passive"))
      (node (ref "STRENGTH_SIGNAL_DRIVE_2") (pin "14") (pinfunction "DRAIN7_14") (pintype "output"))
    )
    (net (code "109") (name "TWI_SCL") (class "Default")
      (node (ref "IC1") (pin "18") (pinfunction "PD0(INT0/OC0B)_18") (pintype "bidirectional"))
      (node (ref "MAIN_DIRECTION_DRIVE") (pin "15") (pinfunction "SCL_15") (pintype "input"))
      (node (ref "MISC_LED_DRIVE") (pin "15") (pinfunction "SCL_15") (pintype "input"))
      (node (ref "OTHER_DIRECTION_DRIVE") (pin "15") (pinfunction "SCL_15") (pintype "input"))
      (node (ref "STRENGTH_SIGNAL_DRIVE_1") (pin "15") (pinfunction "SCL_15") (pintype "input"))
      (node (ref "STRENGTH_SIGNAL_DRIVE_2") (pin "15") (pinfunction "SCL_15") (pintype "input"))
      (node (ref "TWI_SCL_PULLUP") (pin "1") (pinfunction "1_1") (pintype "passive"))
    )
    (net (code "110") (name "TWI_SDA") (class "Default")
      (node (ref "IC1") (pin "19") (pinfunction "PD1(INT1/SDA)_19") (pintype "bidirectional"))
      (node (ref "MAIN_DIRECTION_DRIVE") (pin "2") (pinfunction "SDA_2") (pintype "bidirectional"))
      (node (ref "MISC_LED_DRIVE") (pin "2") (pinfunction "SDA_2") (pintype "bidirectional"))
      (node (ref "OTHER_DIRECTION_DRIVE") (pin "2") (pinfunction "SDA_2") (pintype "bidirectional"))
      (node (ref "STRENGTH_SIGNAL_DRIVE_1") (pin "2") (pinfunction "SDA_2") (pintype "bidirectional"))
      (node (ref "STRENGTH_SIGNAL_DRIVE_2") (pin "2") (pinfunction "SDA_2") (pintype "bidirectional"))
      (node (ref "TWI_SDA_PULLUP") (pin "1") (pinfunction "1_1") (pintype "passive"))
    )
    (net (code "111") (name "TYPE_1") (class "Default")
      (node (ref "JP1") (pin "1") (pinfunction "1_1") (pintype "passive"))
      (node (ref "TYPE_RES_1") (pin "2") (pinfunction "2_2") (pintype "passive"))
    )
    (net (code "112") (name "TYPE_2") (class "Default")
      (node (ref "JP1") (pin "2") (pinfunction "2_2") (pintype "passive"))
      (node (ref "TYPE_RES_2") (pin "1") (pinfunction "1_1") (pintype "passive"))
    )
    (net (code "113") (name "TYPE_3") (class "Default")
      (node (ref "JP1") (pin "3") (pinfunction "3_3") (pintype "passive"))
      (node (ref "TYPE_RES_3") (pin "1") (pinfunction "1_1") (pintype "passive"))
    )
    (net (code "114") (name "TYPE_LED0") (class "Default")
      (node (ref "IC1") (pin "28") (pinfunction "PB4(ADC11)_28") (pintype "bidirectional"))
      (node (ref "TYPE_RES_3") (pin "2") (pinfunction "2_2") (pintype "passive"))
    )
    (net (code "115") (name "TYPE_LED1") (class "Default")
      (node (ref "IC1") (pin "29") (pinfunction "PB5(OC1A/OC4B/ADC12)_29") (pintype "bidirectional"))
      (node (ref "TYPE_RES_2") (pin "2") (pinfunction "2_2") (pintype "passive"))
    )
    (net (code "116") (name "TYPE_LED2") (class "Default")
      (node (ref "IC1") (pin "30") (pinfunction "PB6(OC1B/OC4B/ADC13)_30") (pintype "bidirectional"))
      (node (ref "TYPE_RES_1") (pin "1") (pinfunction "1_1") (pintype "passive"))
    )
    (net (code "117") (name "VCC") (class "Default")
      (node (ref "HWB") (pin "2") (pinfunction "2_2") (pintype "passive"))
      (node (ref "IC1") (pin "14") (pinfunction "VCC_14") (pintype "bidirectional"))
      (node (ref "IC1") (pin "24") (pinfunction "AVCC_24") (pintype "bidirectional"))
      (node (ref "IC1") (pin "34") (pinfunction "VCC1_34") (pintype "bidirectional"))
      (node (ref "IC1") (pin "44") (pinfunction "AVCC1_44") (pintype "bidirectional"))
      (node (ref "ISP1") (pin "2") (pinfunction "2_2") (pintype "passive"))
      (node (ref "LOCK_TRANSISTOR") (pin "C") (pinfunction "C_C") (pintype "passive"))
      (node (ref "MAIN_DIRECTION_DRIVE") (pin "1") (pinfunction "VCC_1") (pintype "power_in"))
      (node (ref "MAIN_DIRECTION_DRIVE") (pin "7") (pinfunction "A2_7") (pintype "input"))
      (node (ref "MAIN_DIR_RES") (pin "1") (pinfunction "1_1") (pintype "passive"))
      (node (ref "MISC_LED_DRIVE") (pin "1") (pinfunction "VCC_1") (pintype "power_in"))
      (node (ref "MISC_LED_DRIVE") (pin "10") (pinfunction "A1_10") (pintype "input"))
      (node (ref "MISC_LED_RES") (pin "1") (pinfunction "1_1") (pintype "passive"))
      (node (ref "OTHER_DIRECTION_DRIVE") (pin "1") (pinfunction "VCC_1") (pintype "power_in"))
      (node (ref "OTHER_DIRECTION_DRIVE") (pin "10") (pinfunction "A1_10") (pintype "input"))
      (node (ref "OTHER_DIRECTION_DRIVE") (pin "9") (pinfunction "A0_9") (pintype "input"))
      (node (ref "OTHER_DIR_RES") (pin "1") (pinfunction "1_1") (pintype "passive"))
      (node (ref "PWR_LED_RES") (pin "2") (pinfunction "2_2") (pintype "passive"))
      (node (ref "RIPPLE_CAP") (pin "1") (pinfunction "1_1") (pintype "passive"))
      (node (ref "SIG_STR_RES_1") (pin "1") (pinfunction "1_1") (pintype "passive"))
      (node (ref "SIG_STR_RES_2") (pin "1") (pinfunction "1_1") (pintype "passive"))
      (node (ref "STRENGTH_SIGNAL_DRIVE_1") (pin "1") (pinfunction "VCC_1") (pintype "power_in"))
      (node (ref "STRENGTH_SIGNAL_DRIVE_2") (pin "1") (pinfunction "VCC_1") (pintype "power_in"))
      (node (ref "STRENGTH_SIGNAL_DRIVE_2") (pin "9") (pinfunction "A0_9") (pintype "input"))
      (node (ref "TWI_SCL_PULLUP") (pin "2") (pinfunction "2_2") (pintype "passive"))
      (node (ref "TWI_SDA_PULLUP") (pin "2") (pinfunction "2_2") (pintype "passive"))
      (node (ref "VOLT_REG") (pin "3") (pinfunction "VO_3") (pintype "passive"))
    )
    (net (code "118") (name "unconnected-(IC1-AREF-Pad42)") (class "Default")
      (node (ref "IC1") (pin "42") (pinfunction "AREF_42") (pintype "bidirectional"))
    )
    (net (code "119") (name "unconnected-(IC1-PB7(OC0A{slash}OC1C{slash}RTS)-Pad12)") (class "Default")
      (node (ref "IC1") (pin "12") (pinfunction "PB7(OC0A/OC1C/RTS)_12") (pintype "bidirectional"))
    )
    (net (code "120") (name "unconnected-(IC1-PC6(OC1A)-Pad31)") (class "Default")
      (node (ref "IC1") (pin "31") (pinfunction "PC6(OC1A)_31") (pintype "bidirectional"))
    )
    (net (code "121") (name "unconnected-(IC1-PC7(ICP3{slash}CLK0{slash}OC4A)-Pad32)") (class "Default")
      (node (ref "IC1") (pin "32") (pinfunction "PC7(ICP3/CLK0/OC4A)_32") (pintype "bidirectional"))
    )
    (net (code "122") (name "unconnected-(IC1-PD2(INT2{slash}RXD1)-Pad20)") (class "Default")
      (node (ref "IC1") (pin "20") (pinfunction "PD2(INT2/RXD1)_20") (pintype "bidirectional"))
    )
    (net (code "123") (name "unconnected-(IC1-PD3(INT3{slash}TXD1)-Pad21)") (class "Default")
      (node (ref "IC1") (pin "21") (pinfunction "PD3(INT3/TXD1)_21") (pintype "bidirectional"))
    )
    (net (code "124") (name "unconnected-(IC1-PD4(ICP1{slash}ADC8)-Pad25)") (class "Default")
      (node (ref "IC1") (pin "25") (pinfunction "PD4(ICP1/ADC8)_25") (pintype "bidirectional"))
    )
    (net (code "125") (name "unconnected-(IC1-PD5(XCK{slash}CTS)-Pad22)") (class "Default")
      (node (ref "IC1") (pin "22") (pinfunction "PD5(XCK/CTS)_22") (pintype "bidirectional"))
    )
    (net (code "126") (name "unconnected-(IC1-PD6(T1{slash}OC4D{slash}ADC9)-Pad26)") (class "Default")
      (node (ref "IC1") (pin "26") (pinfunction "PD6(T1/OC4D/ADC9)_26") (pintype "bidirectional"))
    )
    (net (code "127") (name "unconnected-(IC1-PD7(OC4D{slash}ADC10{slash}T0)-Pad27)") (class "Default")
      (node (ref "IC1") (pin "27") (pinfunction "PD7(OC4D/ADC10/T0)_27") (pintype "bidirectional"))
    )
    (net (code "128") (name "unconnected-(IC1-PE6-Pad1)") (class "Default")
      (node (ref "IC1") (pin "1") (pinfunction "PE6_1") (pintype "bidirectional"))
    )
    (net (code "129") (name "unconnected-(IC1-PF0(ADC0)-Pad41)") (class "Default")
      (node (ref "IC1") (pin "41") (pinfunction "PF0(ADC0)_41") (pintype "bidirectional"))
    )
    (net (code "130") (name "unconnected-(IC1-PF1(ADC1)-Pad40)") (class "Default")
      (node (ref "IC1") (pin "40") (pinfunction "PF1(ADC1)_40") (pintype "bidirectional"))
    )
    (net (code "131") (name "unconnected-(IC1-PF4(ADC4{slash}TCK)-Pad39)") (class "Default")
      (node (ref "IC1") (pin "39") (pinfunction "PF4(ADC4/TCK)_39") (pintype "bidirectional"))
    )
    (net (code "132") (name "unconnected-(IC1-PF5(ADC5{slash}TMS)-Pad38)") (class "Default")
      (node (ref "IC1") (pin "38") (pinfunction "PF5(ADC5/TMS)_38") (pintype "bidirectional"))
    )
    (net (code "133") (name "unconnected-(IC1-PF6(ADC6{slash}TDO)-Pad37)") (class "Default")
      (node (ref "IC1") (pin "37") (pinfunction "PF6(ADC6/TDO)_37") (pintype "bidirectional"))
    )
    (net (code "134") (name "unconnected-(IC1-PF7(ADC7(TDI)-Pad36)") (class "Default")
      (node (ref "IC1") (pin "36") (pinfunction "PF7(ADC7(TDI)_36") (pintype "bidirectional"))
    )
    (net (code "135") (name "unconnected-(USB-PadID)") (class "Default")
      (node (ref "USB") (pin "ID") (pinfunction "ID_ID") (pintype "bidirectional"))
    )
  )
)
